# Fri3D_2018_POWER_01.net
KiCad netlist of a schematic drawn in Altium Designer
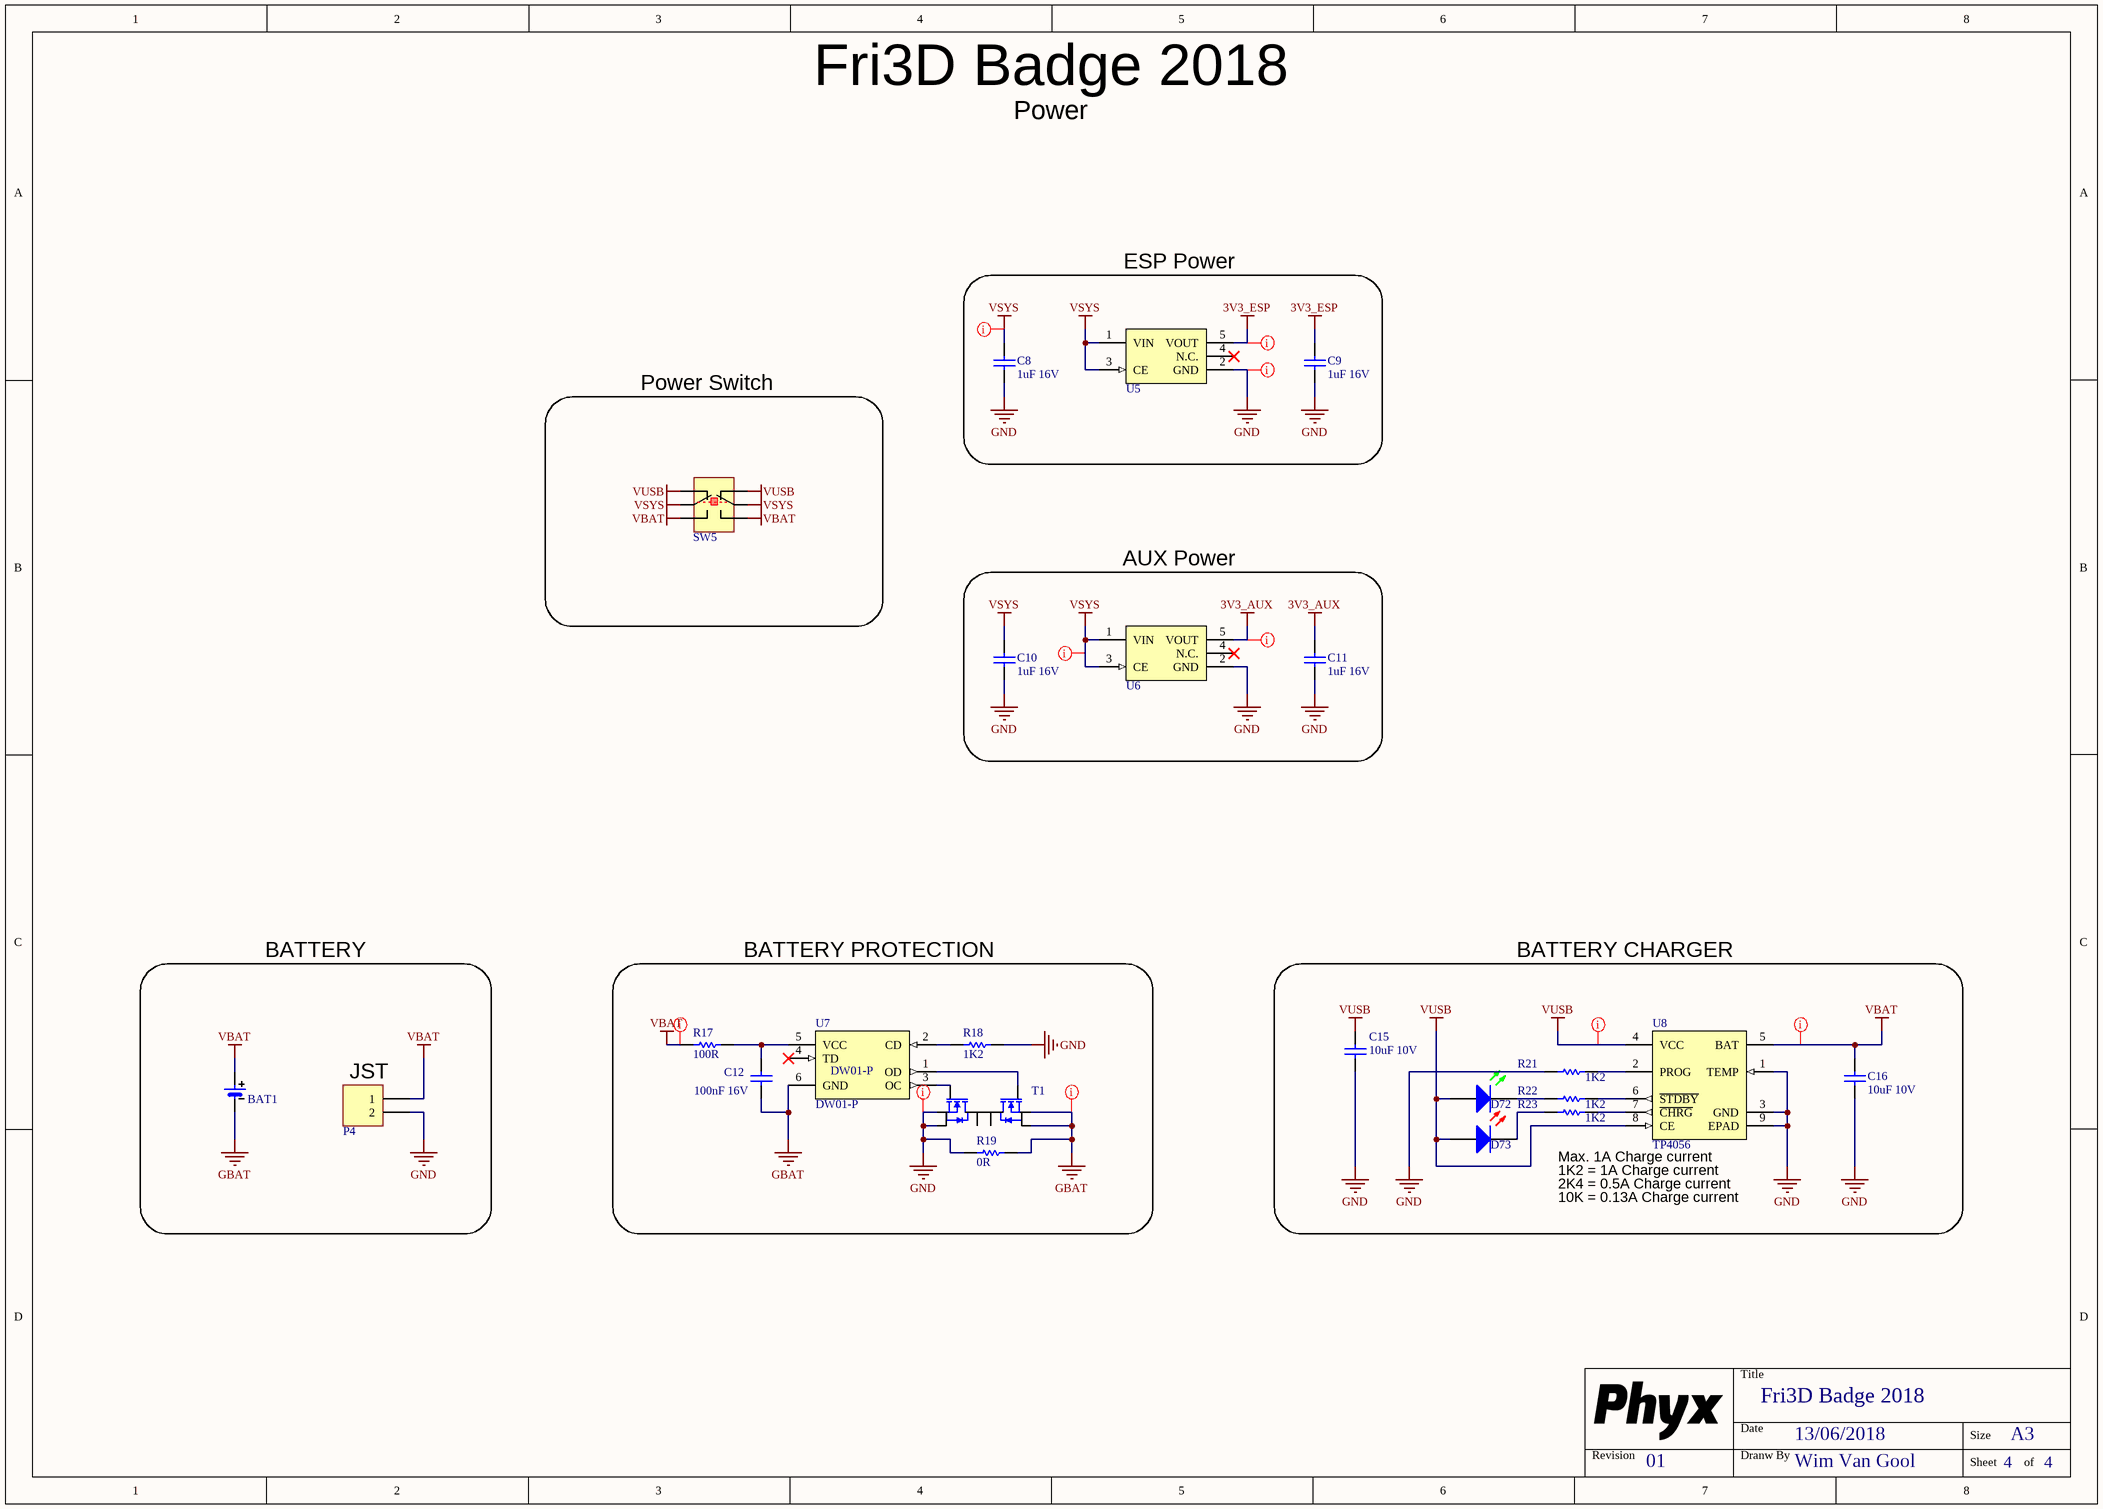
[diagram p0: Fri3D_2018_POWER_01.SchDoc]

(export (version "E")
  (design (tool "Eeschema 10.0.6"))
  (components
    (comp (ref "BAT1")
      (value "18650 Battery holder")
      (footprint "MPD_BH-18650-PC")
      (description "=Description")
      (libsource (lib "Phyx_Components") (part "BAT_2"))
    )
    (comp (ref "C8")
      (value "1uF 16V")
      (footprint "C0603_N")
      (description "Capacitor Ceramic")
      (fields (field (name "Comment") "CAP_CERAMIC"))
      (libsource (lib "Phyx_Components") (part "CAP_CERAMIC"))
    )
    (comp (ref "C9")
      (value "1uF 16V")
      (footprint "C0603_N")
      (description "Capacitor Ceramic")
      (fields (field (name "Comment") "CAP_CERAMIC"))
      (libsource (lib "Phyx_Components") (part "CAP_CERAMIC"))
    )
    (comp (ref "C10")
      (value "1uF 16V")
      (footprint "C0603_N")
      (description "Capacitor Ceramic")
      (fields (field (name "Comment") "CAP_CERAMIC"))
      (libsource (lib "Phyx_Components") (part "CAP_CERAMIC"))
    )
    (comp (ref "C11")
      (value "1uF 16V")
      (footprint "C0603_N")
      (description "Capacitor Ceramic")
      (fields (field (name "Comment") "CAP_CERAMIC"))
      (libsource (lib "Phyx_Components") (part "CAP_CERAMIC"))
    )
    (comp (ref "C12")
      (value "100nF 16V")
      (footprint "C0603_N")
      (description "Capacitor Ceramic")
      (libsource (lib "Phyx_Components") (part "CAP_CERAMIC"))
    )
    (comp (ref "C15")
      (value "10uF 10V")
      (footprint "C0805_N")
      (description "Capacitor Ceramic")
      (fields (field (name "Comment") "CAP_CERAMIC"))
      (libsource (lib "Phyx_Components") (part "CAP_CERAMIC"))
    )
    (comp (ref "C16")
      (value "10uF 10V")
      (footprint "C0805_N")
      (description "Capacitor Ceramic")
      (fields (field (name "Comment") "CAP_CERAMIC"))
      (libsource (lib "Phyx_Components") (part "CAP_CERAMIC"))
    )
    (comp (ref "D72")
      (value "Default 0805 Green LED")
      (footprint "LED_0805_GR")
      (description "=Description")
      (libsource (lib "Phyx_Components") (part "LED_GREEN"))
    )
    (comp (ref "D73")
      (value "Default 0805 Red LED")
      (footprint "LED_0805_RD")
      (description "=Description")
      (libsource (lib "Phyx_Components") (part "LED_RED"))
    )
    (comp (ref "P4")
      (value "Header 2.0mm Shrouded 2")
      (footprint "WE_620102131822")
      (libsource (lib "Phyx_Components") (part "Header 2"))
    )
    (comp (ref "R17")
      (value "100R")
      (footprint "R0603_N")
      (fields (field (name "Comment") "RESISTOR"))
      (libsource (lib "Phyx_Components") (part "RESISTOR"))
    )
    (comp (ref "R18")
      (value "1K2")
      (footprint "R0603_N")
      (fields (field (name "Comment") "RESISTOR"))
      (libsource (lib "Phyx_Components") (part "RESISTOR"))
    )
    (comp (ref "R19")
      (value "0R")
      (footprint "R0603_N")
      (libsource (lib "Phyx_Components") (part "RESISTOR"))
    )
    (comp (ref "R21")
      (value "1K2")
      (footprint "R0603_N")
      (fields (field (name "Comment") "RESISTOR"))
      (libsource (lib "Phyx_Components") (part "RESISTOR"))
    )
    (comp (ref "R22")
      (value "1K2")
      (footprint "R0603_N")
      (fields (field (name "Comment") "RESISTOR"))
      (libsource (lib "Phyx_Components") (part "RESISTOR"))
    )
    (comp (ref "R23")
      (value "1K2")
      (footprint "R0603_N")
      (fields (field (name "Comment") "RESISTOR"))
      (libsource (lib "Phyx_Components") (part "RESISTOR"))
    )
    (comp (ref "SW5")
      (value "Mini slide switch 2P2T")
      (footprint "MSS22D18")
      (libsource (lib "Phyx_Components") (part "SW_2P2T"))
    )
    (comp (ref "T1")
      (value "Dual N-Ch MOSFET Common Drain")
      (footprint "TSSOP_8_65P")
      (description "=Description")
      (libsource (lib "Phyx_Components") (part "N_MOSFET_FS8205A"))
    )
    (comp (ref "U5")
      (value "3V3 LDO 700mA 50mV")
      (footprint "SOT23-5")
      (description "=Designator")
      (libsource (lib "Phyx_Components") (part "XC6210_SOT"))
    )
    (comp (ref "U6")
      (value "3V3 LDO 700mA 50mV")
      (footprint "SOT23-5")
      (description "=Designator")
      (libsource (lib "Phyx_Components") (part "XC6210_SOT"))
    )
    (comp (ref "U7")
      (value "DW01-P")
      (footprint "SOT23-6")
      (description "=Description")
      (fields (field (name "Comment") "DW01-P single cell lithium protection"))
      (libsource (lib "Phyx_Components") (part "DW01-P"))
    )
    (comp (ref "U8")
      (value "TP4056")
      (footprint "SOIC_N_8_TH")
      (description "=Description")
      (fields (field (name "Comment") "Single Cell LiIon charger max 1A"))
      (libsource (lib "Phyx_Components") (part "TP4056"))
    )
  )
  (nets
    (net (code "1") (name "3V3_AUX") (class "Default")
      (node (ref "C11") (pin "1") (pinfunction "1_1") (pintype "passive"))
      (node (ref "U6") (pin "5") (pinfunction "VOUT_5") (pintype "power_in"))
    )
    (net (code "2") (name "3V3_ESP") (class "Default")
      (node (ref "C9") (pin "1") (pinfunction "1_1") (pintype "passive"))
      (node (ref "U5") (pin "5") (pinfunction "VOUT_5") (pintype "power_in"))
    )
    (net (code "3") (name "GBAT") (class "Default")
      (node (ref "BAT1") (pin "2") (pinfunction "2_2") (pintype "passive"))
      (node (ref "C12") (pin "2") (pinfunction "2_2") (pintype "passive"))
      (node (ref "R19") (pin "1") (pinfunction "1_1") (pintype "passive"))
      (node (ref "T1") (pin "2") (pinfunction "S1_2") (pintype "passive"))
      (node (ref "T1") (pin "3") (pinfunction "S1_3") (pintype "passive"))
      (node (ref "U7") (pin "6") (pinfunction "GND_6") (pintype "power_in"))
    )
    (net (code "4") (name "GND") (class "Default")
      (node (ref "C10") (pin "2") (pinfunction "2_2") (pintype "passive"))
      (node (ref "C11") (pin "2") (pinfunction "2_2") (pintype "passive"))
      (node (ref "C15") (pin "2") (pinfunction "2_2") (pintype "passive"))
      (node (ref "C16") (pin "2") (pinfunction "2_2") (pintype "passive"))
      (node (ref "C8") (pin "2") (pinfunction "2_2") (pintype "passive"))
      (node (ref "C9") (pin "2") (pinfunction "2_2") (pintype "passive"))
      (node (ref "P4") (pin "2") (pinfunction "2_2") (pintype "passive"))
      (node (ref "R18") (pin "2") (pinfunction "2_2") (pintype "passive"))
      (node (ref "R19") (pin "2") (pinfunction "2_2") (pintype "passive"))
      (node (ref "R21") (pin "2") (pinfunction "2_2") (pintype "passive"))
      (node (ref "T1") (pin "6") (pinfunction "S2_6") (pintype "passive"))
      (node (ref "T1") (pin "7") (pinfunction "S2_7") (pintype "passive"))
      (node (ref "U5") (pin "2") (pinfunction "GND_2") (pintype "power_in"))
      (node (ref "U6") (pin "2") (pinfunction "GND_2") (pintype "power_in"))
      (node (ref "U8") (pin "1") (pinfunction "TEMP_1") (pintype "input"))
      (node (ref "U8") (pin "3") (pinfunction "GND_3") (pintype "power_in"))
      (node (ref "U8") (pin "9") (pinfunction "EPAD_9") (pintype "power_in"))
    )
    (net (code "5") (name "Net-(D72-K)") (class "Default")
      (node (ref "D72") (pin "2") (pinfunction "K_2") (pintype "passive"))
      (node (ref "R22") (pin "1") (pinfunction "1_1") (pintype "passive"))
    )
    (net (code "6") (name "Net-(D73-K)") (class "Default")
      (node (ref "D73") (pin "2") (pinfunction "K_2") (pintype "passive"))
      (node (ref "R23") (pin "1") (pinfunction "1_1") (pintype "passive"))
    )
    (net (code "7") (name "Net-(T1-G1)") (class "Default")
      (node (ref "T1") (pin "4") (pinfunction "G1_4") (pintype "passive"))
      (node (ref "U7") (pin "1") (pinfunction "OD_1") (pintype "output"))
    )
    (net (code "8") (name "Net-(T1-G2)") (class "Default")
      (node (ref "T1") (pin "5") (pinfunction "G2_5") (pintype "passive"))
      (node (ref "U7") (pin "3") (pinfunction "OC_3") (pintype "output"))
    )
    (net (code "9") (name "Net-(U7-CD)") (class "Default")
      (node (ref "R18") (pin "1") (pinfunction "1_1") (pintype "passive"))
      (node (ref "U7") (pin "2") (pinfunction "CD_2") (pintype "input"))
    )
    (net (code "10") (name "Net-(U7-VCC)") (class "Default")
      (node (ref "C12") (pin "1") (pinfunction "1_1") (pintype "passive"))
      (node (ref "R17") (pin "2") (pinfunction "2_2") (pintype "passive"))
      (node (ref "U7") (pin "5") (pinfunction "VCC_5") (pintype "power_in"))
    )
    (net (code "11") (name "Net-(U8-PROG)") (class "Default")
      (node (ref "R21") (pin "1") (pinfunction "1_1") (pintype "passive"))
      (node (ref "U8") (pin "2") (pinfunction "PROG_2") (pintype "passive"))
    )
    (net (code "12") (name "Net-(U8-~{CHRG})") (class "Default")
      (node (ref "R23") (pin "2") (pinfunction "2_2") (pintype "passive"))
      (node (ref "U8") (pin "7") (pinfunction "~{CHRG}_7") (pintype "output"))
    )
    (net (code "13") (name "Net-(U8-~{STDBY})") (class "Default")
      (node (ref "R22") (pin "2") (pinfunction "2_2") (pintype "passive"))
      (node (ref "U8") (pin "6") (pinfunction "~{STDBY}_6") (pintype "output"))
    )
    (net (code "14") (name "VBAT") (class "Default")
      (node (ref "BAT1") (pin "1") (pinfunction "1_1") (pintype "passive"))
      (node (ref "C16") (pin "1") (pinfunction "1_1") (pintype "passive"))
      (node (ref "P4") (pin "1") (pinfunction "1_1") (pintype "passive"))
      (node (ref "R17") (pin "1") (pinfunction "1_1") (pintype "passive"))
      (node (ref "SW5") (pin "5") (pinfunction "5_5") (pintype "passive"))
      (node (ref "SW5") (pin "6") (pinfunction "5_6") (pintype "passive"))
      (node (ref "U8") (pin "5") (pinfunction "BAT_5") (pintype "power_in"))
    )
    (net (code "15") (name "VSYS") (class "Default")
      (node (ref "C10") (pin "1") (pinfunction "1_1") (pintype "passive"))
      (node (ref "C8") (pin "1") (pinfunction "1_1") (pintype "passive"))
      (node (ref "SW5") (pin "3") (pinfunction "3_3") (pintype "passive"))
      (node (ref "SW5") (pin "4") (pinfunction "4_4") (pintype "passive"))
      (node (ref "U5") (pin "1") (pinfunction "VIN_1") (pintype "power_in"))
      (node (ref "U5") (pin "3") (pinfunction "CE_3") (pintype "input"))
      (node (ref "U6") (pin "1") (pinfunction "VIN_1") (pintype "power_in"))
      (node (ref "U6") (pin "3") (pinfunction "CE_3") (pintype "input"))
    )
    (net (code "16") (name "VUSB") (class "Default")
      (node (ref "C15") (pin "1") (pinfunction "1_1") (pintype "passive"))
      (node (ref "D72") (pin "1") (pinfunction "A_1") (pintype "passive"))
      (node (ref "D73") (pin "1") (pinfunction "A_1") (pintype "passive"))
      (node (ref "SW5") (pin "1") (pinfunction "1_1") (pintype "passive"))
      (node (ref "SW5") (pin "2") (pinfunction "2_2") (pintype "passive"))
      (node (ref "U8") (pin "4") (pinfunction "VCC_4") (pintype "power_in"))
      (node (ref "U8") (pin "8") (pinfunction "CE_8") (pintype "input"))
    )
    (net (code "17") (name "unconnected-(T1-D1-Pad1)") (class "Default")
      (node (ref "T1") (pin "1") (pinfunction "D1_1") (pintype "passive"))
    )
    (net (code "18") (name "unconnected-(T1-D2-Pad8)") (class "Default")
      (node (ref "T1") (pin "8") (pinfunction "D2_8") (pintype "passive"))
    )
    (net (code "19") (name "unconnected-(U5-N.C.-Pad4)") (class "Default")
      (node (ref "U5") (pin "4") (pinfunction "N.C._4") (pintype "passive+no_connect"))
    )
    (net (code "20") (name "unconnected-(U6-N.C.-Pad4)") (class "Default")
      (node (ref "U6") (pin "4") (pinfunction "N.C._4") (pintype "passive+no_connect"))
    )
    (net (code "21") (name "unconnected-(U7-TD-Pad4)") (class "Default")
      (node (ref "U7") (pin "4") (pinfunction "TD_4") (pintype "input+no_connect"))
    )
  )
)
